# Zed_Camera.net
KiCad netlist of a schematic drawn in EAGLE
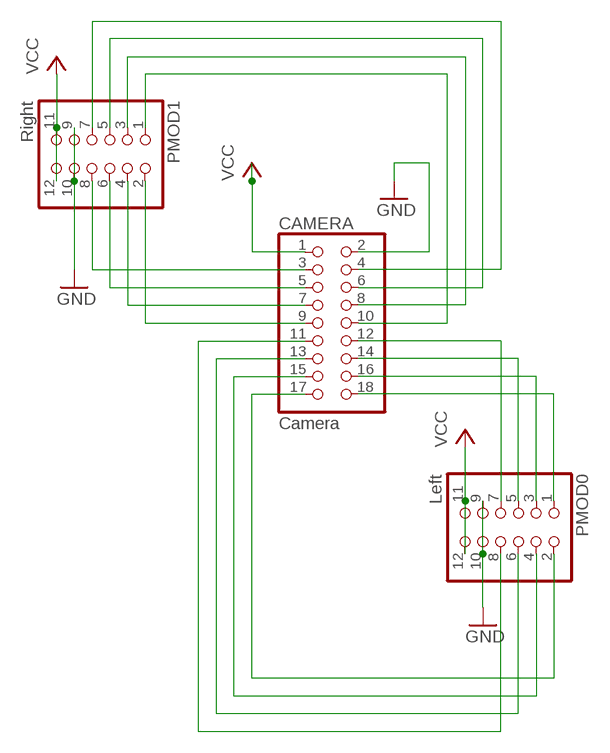
[diagram p0: schematic, sheet 1]

(export (version "E")
  (design (tool "Eeschema 10.0.6"))
  (components
    (comp (ref "CAMERA")
      (value "Camera")
      (footprint "eagle-import:2X09")
      (libsource (lib "eagle-import") (part "PINHD-2X9"))
    )
    (comp (ref "PMOD0")
      (value "Left")
      (footprint "eagle-import:2X06")
      (libsource (lib "eagle-import") (part "PINHD-2X6"))
    )
    (comp (ref "PMOD1")
      (value "Right")
      (footprint "eagle-import:2X06")
      (libsource (lib "eagle-import") (part "PINHD-2X6"))
    )
  )
  (nets
    (net (code "1") (name "GND") (class "Default")
      (node (ref "CAMERA") (pin "2") (pinfunction "2_2") (pintype "passive"))
      (node (ref "PMOD0") (pin "10") (pinfunction "10_10") (pintype "passive"))
      (node (ref "PMOD0") (pin "9") (pinfunction "9_9") (pintype "passive"))
      (node (ref "PMOD1") (pin "10") (pinfunction "10_10") (pintype "passive"))
      (node (ref "PMOD1") (pin "9") (pinfunction "9_9") (pintype "passive"))
    )
    (net (code "2") (name "Net-(CAMERA-Pad3)") (class "Default")
      (node (ref "CAMERA") (pin "3") (pinfunction "3_3") (pintype "passive"))
      (node (ref "PMOD1") (pin "8") (pinfunction "8_8") (pintype "passive"))
    )
    (net (code "3") (name "Net-(CAMERA-Pad4)") (class "Default")
      (node (ref "CAMERA") (pin "4") (pinfunction "4_4") (pintype "passive"))
      (node (ref "PMOD1") (pin "7") (pinfunction "7_7") (pintype "passive"))
    )
    (net (code "4") (name "Net-(CAMERA-Pad5)") (class "Default")
      (node (ref "CAMERA") (pin "5") (pinfunction "5_5") (pintype "passive"))
      (node (ref "PMOD1") (pin "6") (pinfunction "6_6") (pintype "passive"))
    )
    (net (code "5") (name "Net-(CAMERA-Pad6)") (class "Default")
      (node (ref "CAMERA") (pin "6") (pinfunction "6_6") (pintype "passive"))
      (node (ref "PMOD1") (pin "5") (pinfunction "5_5") (pintype "passive"))
    )
    (net (code "6") (name "Net-(CAMERA-Pad7)") (class "Default")
      (node (ref "CAMERA") (pin "7") (pinfunction "7_7") (pintype "passive"))
      (node (ref "PMOD1") (pin "4") (pinfunction "4_4") (pintype "passive"))
    )
    (net (code "7") (name "Net-(CAMERA-Pad8)") (class "Default")
      (node (ref "CAMERA") (pin "8") (pinfunction "8_8") (pintype "passive"))
      (node (ref "PMOD1") (pin "3") (pinfunction "3_3") (pintype "passive"))
    )
    (net (code "8") (name "Net-(CAMERA-Pad9)") (class "Default")
      (node (ref "CAMERA") (pin "9") (pinfunction "9_9") (pintype "passive"))
      (node (ref "PMOD1") (pin "2") (pinfunction "2_2") (pintype "passive"))
    )
    (net (code "9") (name "Net-(CAMERA-Pad10)") (class "Default")
      (node (ref "CAMERA") (pin "10") (pinfunction "10_10") (pintype "passive"))
      (node (ref "PMOD1") (pin "1") (pinfunction "1_1") (pintype "passive"))
    )
    (net (code "10") (name "Net-(CAMERA-Pad11)") (class "Default")
      (node (ref "CAMERA") (pin "11") (pinfunction "11_11") (pintype "passive"))
      (node (ref "PMOD0") (pin "8") (pinfunction "8_8") (pintype "passive"))
    )
    (net (code "11") (name "Net-(CAMERA-Pad12)") (class "Default")
      (node (ref "CAMERA") (pin "12") (pinfunction "12_12") (pintype "passive"))
      (node (ref "PMOD0") (pin "7") (pinfunction "7_7") (pintype "passive"))
    )
    (net (code "12") (name "Net-(CAMERA-Pad13)") (class "Default")
      (node (ref "CAMERA") (pin "13") (pinfunction "13_13") (pintype "passive"))
      (node (ref "PMOD0") (pin "6") (pinfunction "6_6") (pintype "passive"))
    )
    (net (code "13") (name "Net-(CAMERA-Pad14)") (class "Default")
      (node (ref "CAMERA") (pin "14") (pinfunction "14_14") (pintype "passive"))
      (node (ref "PMOD0") (pin "5") (pinfunction "5_5") (pintype "passive"))
    )
    (net (code "14") (name "Net-(CAMERA-Pad15)") (class "Default")
      (node (ref "CAMERA") (pin "15") (pinfunction "15_15") (pintype "passive"))
      (node (ref "PMOD0") (pin "4") (pinfunction "4_4") (pintype "passive"))
    )
    (net (code "15") (name "Net-(CAMERA-Pad16)") (class "Default")
      (node (ref "CAMERA") (pin "16") (pinfunction "16_16") (pintype "passive"))
      (node (ref "PMOD0") (pin "3") (pinfunction "3_3") (pintype "passive"))
    )
    (net (code "16") (name "Net-(CAMERA-Pad17)") (class "Default")
      (node (ref "CAMERA") (pin "17") (pinfunction "17_17") (pintype "passive"))
      (node (ref "PMOD0") (pin "2") (pinfunction "2_2") (pintype "passive"))
    )
    (net (code "17") (name "Net-(CAMERA-Pad18)") (class "Default")
      (node (ref "CAMERA") (pin "18") (pinfunction "18_18") (pintype "passive"))
      (node (ref "PMOD0") (pin "1") (pinfunction "1_1") (pintype "passive"))
    )
    (net (code "18") (name "VCC") (class "Default")
      (node (ref "CAMERA") (pin "1") (pinfunction "1_1") (pintype "passive"))
      (node (ref "PMOD0") (pin "11") (pinfunction "11_11") (pintype "passive"))
      (node (ref "PMOD0") (pin "12") (pinfunction "12_12") (pintype "passive"))
      (node (ref "PMOD1") (pin "11") (pinfunction "11_11") (pintype "passive"))
      (node (ref "PMOD1") (pin "12") (pinfunction "12_12") (pintype "passive"))
    )
  )
)
